# Processor.net
KiCad netlist of a schematic drawn in Altium Designer
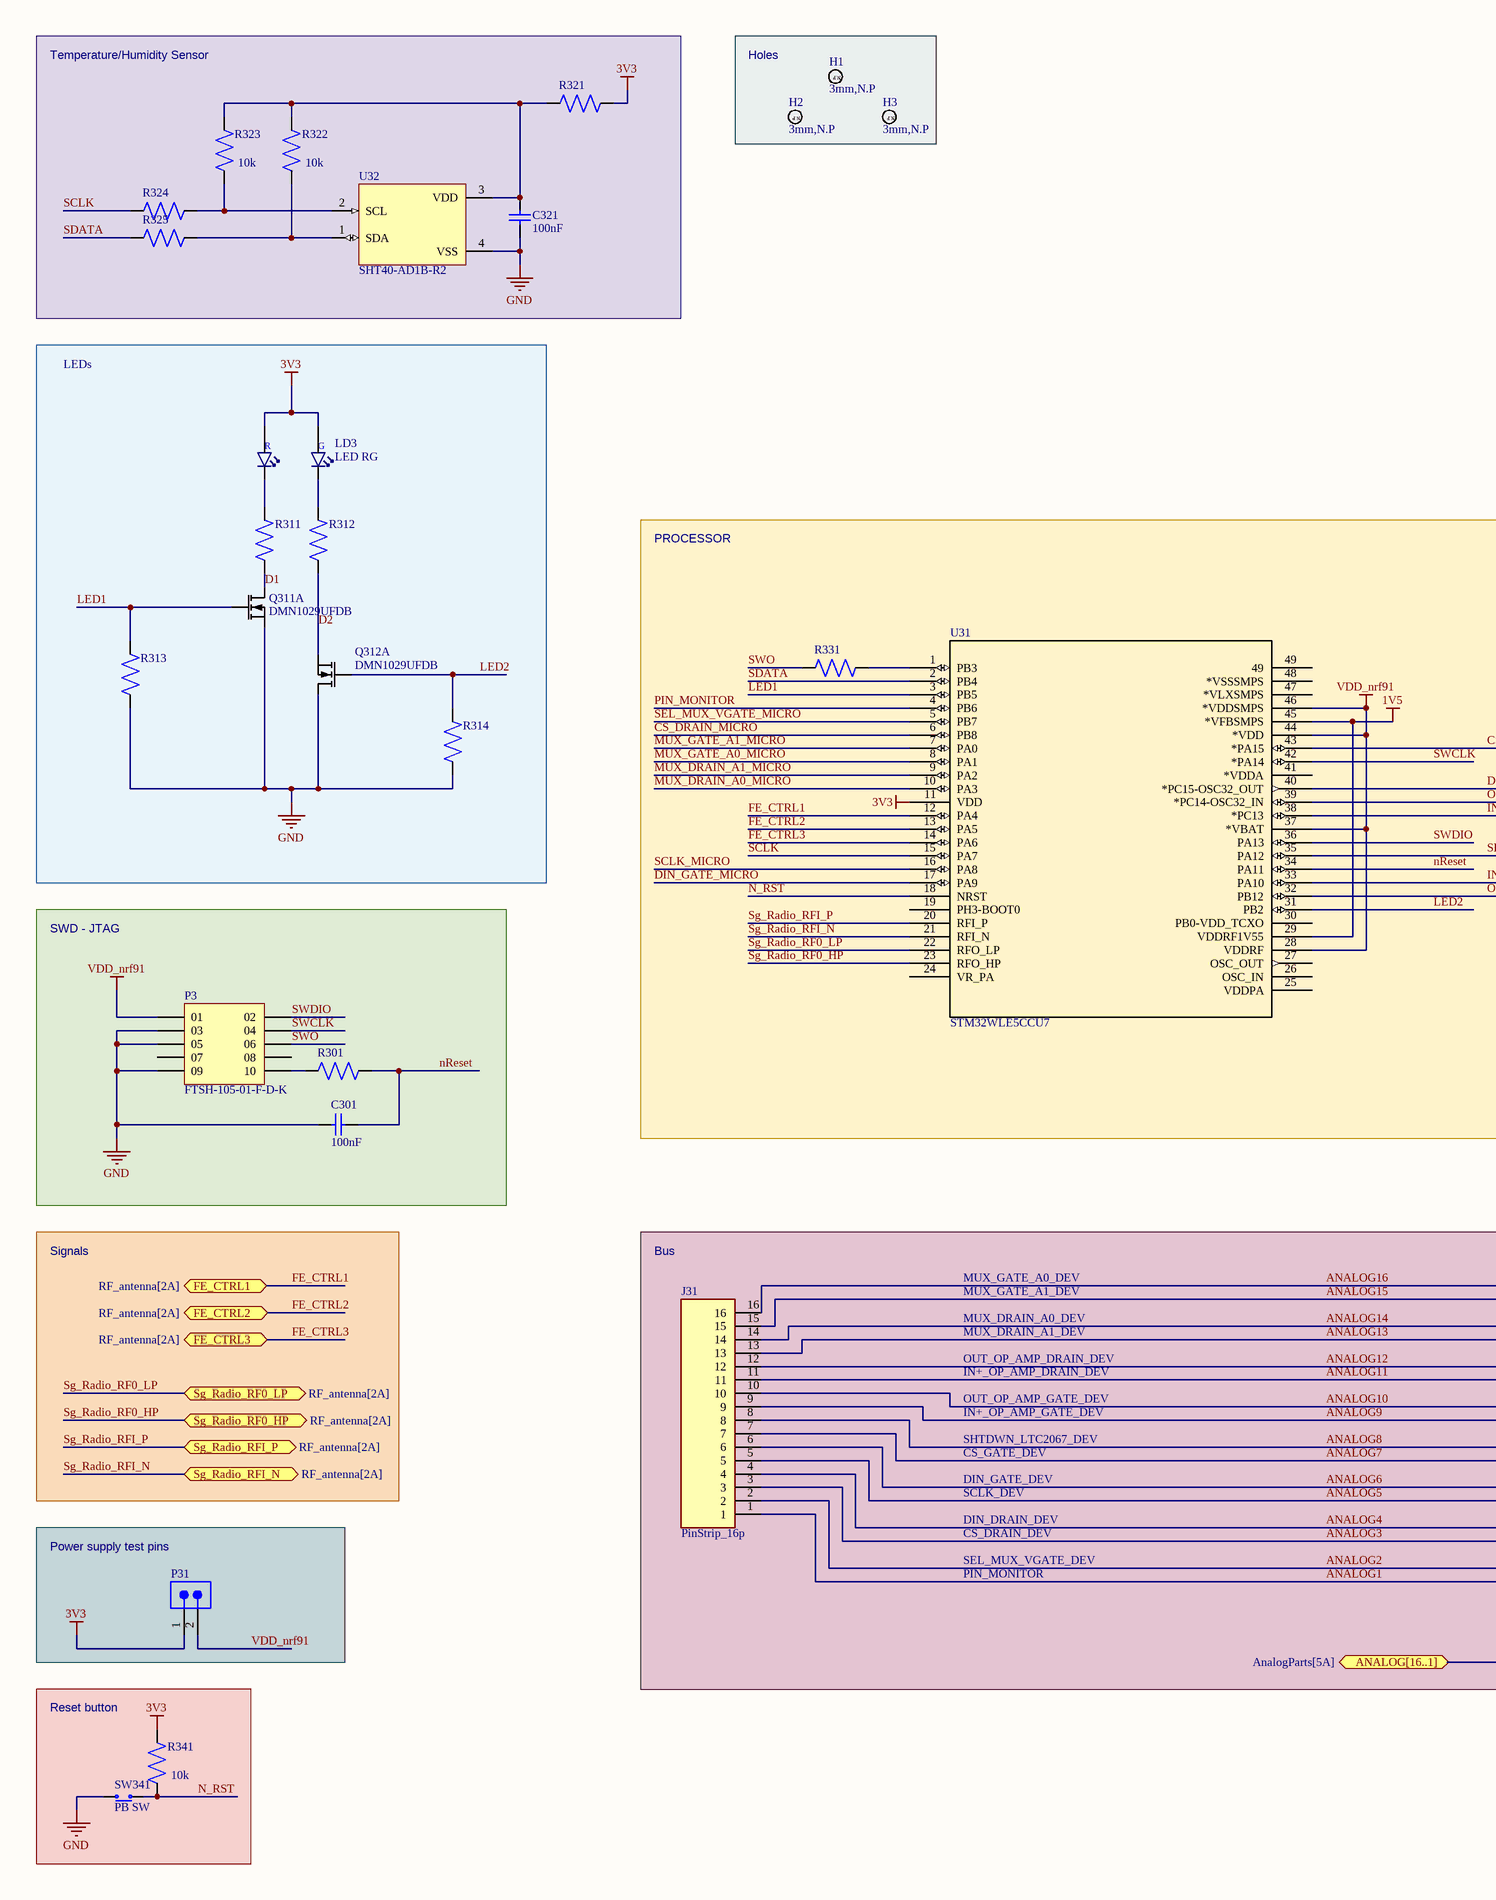
[diagram p0: Processor.SchDoc, left]
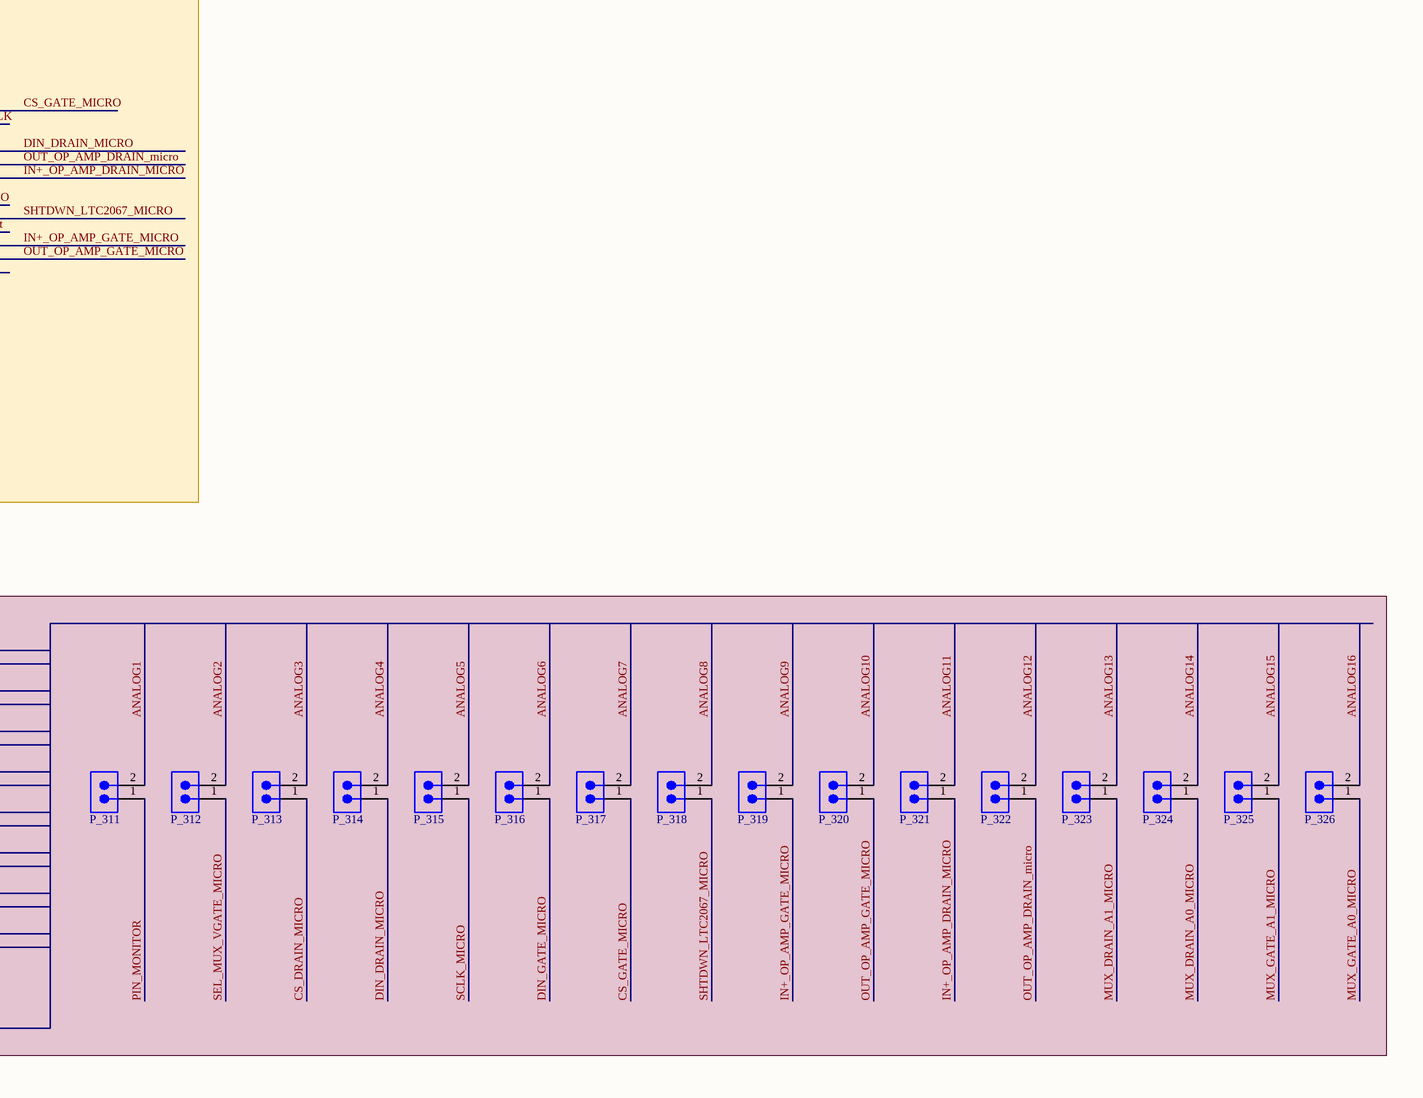
[diagram p1: Processor.SchDoc, right]

(export (version "E")
  (design (tool "Eeschema 10.0.6"))
  (components
    (comp (ref "C301")
      (value "100nF")
      (footprint "CAPC1608X06L")
      (description "Capacitor, X5R, ±10%")
      (libsource (lib "ProgettoAgrifoodLibreriaSCH") (part "C0603-4µ7"))
    )
    (comp (ref "C321")
      (value "100nF")
      (footprint "CAPC1608X06L")
      (description "Capacitor, X5R, ±10%")
      (libsource (lib "ProgettoAgrifoodLibreriaSCH") (part "C0603-4µ7"))
    )
    (comp (ref "H1")
      (value "3mm,N.P")
      (footprint "HOLE_NP_3MM")
      (description "Regular Non-Plated, 3mm hole")
      (libsource (lib "ProgettoAgrifoodLibreriaSCH") (part "Hole_3MM_NP"))
    )
    (comp (ref "H2")
      (value "3mm,N.P")
      (footprint "HOLE_NP_3MM")
      (description "Regular Non-Plated, 3mm hole")
      (libsource (lib "ProgettoAgrifoodLibreriaSCH") (part "Hole_3MM_NP"))
    )
    (comp (ref "H3")
      (value "3mm,N.P")
      (footprint "HOLE_NP_3MM")
      (description "Regular Non-Plated, 3mm hole")
      (libsource (lib "ProgettoAgrifoodLibreriaSCH") (part "Hole_3MM_NP"))
    )
    (comp (ref "J31")
      (value "PinStrip_16p")
      (footprint "PinStrip_16p")
      (description "Connector")
      (fields (field (name "MANUFACTURER_PART_NUMBER") "PH1-16-UA"))
      (libsource (lib "add2") (part "PinStrip_16p"))
    )
    (comp (ref "LD3")
      (value "LED RG")
      (footprint "LED_RGB_0805")
      (description "Red green LED 2 mm x 1.25 mm SMD")
      (libsource (lib "ProgettoAgrifoodLibreriaSCH") (part "APHBM2012LSURKZGKC"))
    )
    (comp (ref "P3")
      (value "FTSH-105-01-F-D-K")
      (footprint "HDR_2x5-THT-1.27mm-K")
      (description "Connector Header Through Hole 10 position 0.050 (1.27mm)")
      (fields (field (name "MF") "Samtec"))
      (libsource (lib "ProgettoAgrifoodLibreriaSCH") (part "Pin Header 2x5 THT, 1.27mm KS"))
    )
    (comp (ref "P31")
      (value "Pin header 2p")
      (footprint "Pin_header_1x2")
      (description "Pin Header, THT, Vertical, pitch 2.54mm, 1 Row, 2P")
      (libsource (lib "ProgettoAgrifoodLibreriaSCH") (part "Pin header 2p"))
    )
    (comp (ref "P_311")
      (value "Pin header 2p")
      (footprint "Pin_header_1x2")
      (description "Pin Header, THT, Vertical, pitch 2.54mm, 1 Row, 2P")
      (libsource (lib "ProgettoAgrifoodLibreriaSCH") (part "Pin header 2p"))
    )
    (comp (ref "P_312")
      (value "Pin header 2p")
      (footprint "Pin_header_1x2")
      (description "Pin Header, THT, Vertical, pitch 2.54mm, 1 Row, 2P")
      (libsource (lib "ProgettoAgrifoodLibreriaSCH") (part "Pin header 2p"))
    )
    (comp (ref "P_313")
      (value "Pin header 2p")
      (footprint "Pin_header_1x2")
      (description "Pin Header, THT, Vertical, pitch 2.54mm, 1 Row, 2P")
      (libsource (lib "ProgettoAgrifoodLibreriaSCH") (part "Pin header 2p"))
    )
    (comp (ref "P_314")
      (value "Pin header 2p")
      (footprint "Pin_header_1x2")
      (description "Pin Header, THT, Vertical, pitch 2.54mm, 1 Row, 2P")
      (libsource (lib "ProgettoAgrifoodLibreriaSCH") (part "Pin header 2p"))
    )
    (comp (ref "P_315")
      (value "Pin header 2p")
      (footprint "Pin_header_1x2")
      (description "Pin Header, THT, Vertical, pitch 2.54mm, 1 Row, 2P")
      (libsource (lib "ProgettoAgrifoodLibreriaSCH") (part "Pin header 2p"))
    )
    (comp (ref "P_316")
      (value "Pin header 2p")
      (footprint "Pin_header_1x2")
      (description "Pin Header, THT, Vertical, pitch 2.54mm, 1 Row, 2P")
      (libsource (lib "ProgettoAgrifoodLibreriaSCH") (part "Pin header 2p"))
    )
    (comp (ref "P_317")
      (value "Pin header 2p")
      (footprint "Pin_header_1x2")
      (description "Pin Header, THT, Vertical, pitch 2.54mm, 1 Row, 2P")
      (libsource (lib "ProgettoAgrifoodLibreriaSCH") (part "Pin header 2p"))
    )
    (comp (ref "P_318")
      (value "Pin header 2p")
      (footprint "Pin_header_1x2")
      (description "Pin Header, THT, Vertical, pitch 2.54mm, 1 Row, 2P")
      (libsource (lib "ProgettoAgrifoodLibreriaSCH") (part "Pin header 2p"))
    )
    (comp (ref "P_319")
      (value "Pin header 2p")
      (footprint "Pin_header_1x2")
      (description "Pin Header, THT, Vertical, pitch 2.54mm, 1 Row, 2P")
      (libsource (lib "ProgettoAgrifoodLibreriaSCH") (part "Pin header 2p"))
    )
    (comp (ref "P_320")
      (value "Pin header 2p")
      (footprint "Pin_header_1x2")
      (description "Pin Header, THT, Vertical, pitch 2.54mm, 1 Row, 2P")
      (libsource (lib "ProgettoAgrifoodLibreriaSCH") (part "Pin header 2p"))
    )
    (comp (ref "P_321")
      (value "Pin header 2p")
      (footprint "Pin_header_1x2")
      (description "Pin Header, THT, Vertical, pitch 2.54mm, 1 Row, 2P")
      (libsource (lib "ProgettoAgrifoodLibreriaSCH") (part "Pin header 2p"))
    )
    (comp (ref "P_322")
      (value "Pin header 2p")
      (footprint "Pin_header_1x2")
      (description "Pin Header, THT, Vertical, pitch 2.54mm, 1 Row, 2P")
      (libsource (lib "ProgettoAgrifoodLibreriaSCH") (part "Pin header 2p"))
    )
    (comp (ref "P_323")
      (value "Pin header 2p")
      (footprint "Pin_header_1x2")
      (description "Pin Header, THT, Vertical, pitch 2.54mm, 1 Row, 2P")
      (libsource (lib "ProgettoAgrifoodLibreriaSCH") (part "Pin header 2p"))
    )
    (comp (ref "P_324")
      (value "Pin header 2p")
      (footprint "Pin_header_1x2")
      (description "Pin Header, THT, Vertical, pitch 2.54mm, 1 Row, 2P")
      (libsource (lib "ProgettoAgrifoodLibreriaSCH") (part "Pin header 2p"))
    )
    (comp (ref "P_325")
      (value "Pin header 2p")
      (footprint "Pin_header_1x2")
      (description "Pin Header, THT, Vertical, pitch 2.54mm, 1 Row, 2P")
      (libsource (lib "ProgettoAgrifoodLibreriaSCH") (part "Pin header 2p"))
    )
    (comp (ref "P_326")
      (value "Pin header 2p")
      (footprint "Pin_header_1x2")
      (description "Pin Header, THT, Vertical, pitch 2.54mm, 1 Row, 2P")
      (libsource (lib "ProgettoAgrifoodLibreriaSCH") (part "Pin header 2p"))
    )
    (comp (ref "Q311")
      (value "DMN1029UFDB")
      (footprint "MOSFET_DMP2160UFDB-7")
      (description "Dual N Ch MOFET, 5.6A, 29mOhm max, 1.4W")
      (libsource (lib "ProgettoAgrifoodLibreriaSCH") (part "DMN1029UFDB"))
    )
    (comp (ref "Q312")
      (value "DMN1029UFDB")
      (footprint "MOSFET_DMP2160UFDB-7")
      (description "Dual N Ch MOFET, 5.6A, 29mOhm max, 1.4W")
      (libsource (lib "ProgettoAgrifoodLibreriaSCH") (part "DMN1029UFDB"))
    )
    (comp (ref "R301")
      (value "~")
      (footprint "RESC1608X04.5L")
      (description "Resistor, ±1%, 0.063W")
      (libsource (lib "ProgettoAgrifoodLibreriaSCH") (part "R0603"))
    )
    (comp (ref "R311")
      (value "~")
      (footprint "RESC1608X04.5L")
      (description "Resistor, ±1%, 0.063W")
      (libsource (lib "ProgettoAgrifoodLibreriaSCH") (part "R0603"))
    )
    (comp (ref "R312")
      (value "~")
      (footprint "RESC1608X04.5L")
      (description "Resistor, ±1%, 0.063W")
      (libsource (lib "ProgettoAgrifoodLibreriaSCH") (part "R0603"))
    )
    (comp (ref "R313")
      (value "~")
      (footprint "RESC1608X04.5L")
      (description "Resistor, ±1%, 0.063W")
      (libsource (lib "ProgettoAgrifoodLibreriaSCH") (part "R0603"))
    )
    (comp (ref "R314")
      (value "~")
      (footprint "RESC1608X04.5L")
      (description "Resistor, ±1%, 0.063W")
      (libsource (lib "ProgettoAgrifoodLibreriaSCH") (part "R0603"))
    )
    (comp (ref "R321")
      (value "~")
      (footprint "RESC1608X04.5L")
      (description "Resistor, ±1%, 0.063W")
      (libsource (lib "ProgettoAgrifoodLibreriaSCH") (part "R0603"))
    )
    (comp (ref "R322")
      (value "10k")
      (footprint "RESC1608X04.5L")
      (description "Resistor, ±1%, 0.063W")
      (libsource (lib "ProgettoAgrifoodLibreriaSCH") (part "R0603"))
    )
    (comp (ref "R323")
      (value "10k")
      (footprint "RESC1608X04.5L")
      (description "Resistor, ±1%, 0.063W")
      (libsource (lib "ProgettoAgrifoodLibreriaSCH") (part "R0603"))
    )
    (comp (ref "R324")
      (value "~")
      (footprint "RESC1608X04.5L")
      (description "Resistor, ±1%, 0.063W")
      (libsource (lib "ProgettoAgrifoodLibreriaSCH") (part "R0603"))
    )
    (comp (ref "R325")
      (value "~")
      (footprint "RESC1608X04.5L")
      (description "Resistor, ±1%, 0.063W")
      (libsource (lib "ProgettoAgrifoodLibreriaSCH") (part "R0603"))
    )
    (comp (ref "R331")
      (value "~")
      (footprint "RESC1608X04.5L")
      (description "Resistor, ±1%, 0.063W")
      (libsource (lib "ProgettoAgrifoodLibreriaSCH") (part "R0603"))
    )
    (comp (ref "R341")
      (value "10k")
      (footprint "RESC1608X04.5L")
      (description "Resistor, ±1%, 0.063W")
      (libsource (lib "ProgettoAgrifoodLibreriaSCH") (part "R0603"))
    )
    (comp (ref "SW341")
      (value "PB SW")
      (footprint "Switch-PB-6.2x6.3mm-SMD")
      (description "Tactile Switch, SPNO, SMD, 160gf, 6.2x6.3x2.5mm")
      (libsource (lib "ProgettoAgrifoodLibreriaSCH") (part "Switch-PB-6.2x6.3mm-SMD"))
    )
    (comp (ref "U31")
      (value "STM32WLE5CCU7")
      (footprint "UFQFPN_5CCU7_STM")
      (description "No Description Available")
      (libsource (lib "STM32WLE5CCU7") (part "STM32WLE5CCU7"))
    )
    (comp (ref "U32")
      (value "SHT40-AD1B-R2")
      (footprint "SHT4X")
      (description "Humidity/Temperature Sensor Digital Serial (I2C) 4-Pin DFN EP T/R")
      (fields (field (name "MF") "Sensirion AG"))
      (libsource (lib "ProgettoAgrifoodLibreriaSCH") (part "SHT40-AD1B-R2"))
    )
  )
  (nets
    (net (code "1") (name "/ANALOG1") (class "Default")
      (node (ref "J31") (pin "1") (pinfunction "1_1") (pintype "passive"))
      (node (ref "P_311") (pin "2") (pinfunction "2_2") (pintype "passive"))
    )
    (net (code "2") (name "/ANALOG2") (class "Default")
      (node (ref "J31") (pin "2") (pinfunction "2_2") (pintype "passive"))
      (node (ref "P_312") (pin "2") (pinfunction "2_2") (pintype "passive"))
    )
    (net (code "3") (name "/ANALOG3") (class "Default")
      (node (ref "J31") (pin "3") (pinfunction "3_3") (pintype "passive"))
      (node (ref "P_313") (pin "2") (pinfunction "2_2") (pintype "passive"))
    )
    (net (code "4") (name "/ANALOG4") (class "Default")
      (node (ref "J31") (pin "4") (pinfunction "4_4") (pintype "passive"))
      (node (ref "P_314") (pin "2") (pinfunction "2_2") (pintype "passive"))
    )
    (net (code "5") (name "/ANALOG5") (class "Default")
      (node (ref "J31") (pin "5") (pinfunction "5_5") (pintype "passive"))
      (node (ref "P_315") (pin "2") (pinfunction "2_2") (pintype "passive"))
    )
    (net (code "6") (name "/ANALOG6") (class "Default")
      (node (ref "J31") (pin "6") (pinfunction "6_6") (pintype "passive"))
      (node (ref "P_316") (pin "2") (pinfunction "2_2") (pintype "passive"))
    )
    (net (code "7") (name "/ANALOG7") (class "Default")
      (node (ref "J31") (pin "7") (pinfunction "7_7") (pintype "passive"))
      (node (ref "P_317") (pin "2") (pinfunction "2_2") (pintype "passive"))
    )
    (net (code "8") (name "/ANALOG8") (class "Default")
      (node (ref "J31") (pin "8") (pinfunction "8_8") (pintype "passive"))
      (node (ref "P_318") (pin "2") (pinfunction "2_2") (pintype "passive"))
    )
    (net (code "9") (name "/ANALOG9") (class "Default")
      (node (ref "J31") (pin "9") (pinfunction "9_9") (pintype "passive"))
      (node (ref "P_319") (pin "2") (pinfunction "2_2") (pintype "passive"))
    )
    (net (code "10") (name "/ANALOG10") (class "Default")
      (node (ref "J31") (pin "10") (pinfunction "10_10") (pintype "passive"))
      (node (ref "P_320") (pin "2") (pinfunction "2_2") (pintype "passive"))
    )
    (net (code "11") (name "/ANALOG11") (class "Default")
      (node (ref "J31") (pin "11") (pinfunction "11_11") (pintype "passive"))
      (node (ref "P_321") (pin "2") (pinfunction "2_2") (pintype "passive"))
    )
    (net (code "12") (name "/ANALOG12") (class "Default")
      (node (ref "J31") (pin "12") (pinfunction "12_12") (pintype "passive"))
      (node (ref "P_322") (pin "2") (pinfunction "2_2") (pintype "passive"))
    )
    (net (code "13") (name "/ANALOG13") (class "Default")
      (node (ref "J31") (pin "13") (pinfunction "13_13") (pintype "passive"))
      (node (ref "P_323") (pin "2") (pinfunction "2_2") (pintype "passive"))
    )
    (net (code "14") (name "/ANALOG14") (class "Default")
      (node (ref "J31") (pin "14") (pinfunction "14_14") (pintype "passive"))
      (node (ref "P_324") (pin "2") (pinfunction "2_2") (pintype "passive"))
    )
    (net (code "15") (name "/ANALOG15") (class "Default")
      (node (ref "J31") (pin "15") (pinfunction "15_15") (pintype "passive"))
      (node (ref "P_325") (pin "2") (pinfunction "2_2") (pintype "passive"))
    )
    (net (code "16") (name "/ANALOG16") (class "Default")
      (node (ref "J31") (pin "16") (pinfunction "16_16") (pintype "passive"))
      (node (ref "P_326") (pin "2") (pinfunction "2_2") (pintype "passive"))
    )
    (net (code "18") (name "/CS_DRAIN_MICRO") (class "Default")
      (node (ref "P_313") (pin "1") (pinfunction "1_1") (pintype "passive"))
      (node (ref "U31") (pin "6") (pinfunction "PB8_6") (pintype "bidirectional"))
    )
    (net (code "19") (name "/CS_GATE_MICRO") (class "Default")
      (node (ref "P_317") (pin "1") (pinfunction "1_1") (pintype "passive"))
      (node (ref "U31") (pin "43") (pinfunction "*PA15_43") (pintype "bidirectional"))
    )
    (net (code "20") (name "/D1") (class "Default")
      (node (ref "Q311") (pin "6") (pinfunction "D1_6") (pintype "passive"))
      (node (ref "R311") (pin "1") (pinfunction "1_1") (pintype "passive"))
    )
    (net (code "21") (name "/D2") (class "Default")
      (node (ref "Q312") (pin "1") (pinfunction "S1_1") (pintype "passive"))
      (node (ref "R312") (pin "1") (pinfunction "1_1") (pintype "passive"))
    )
    (net (code "22") (name "/DIN_DRAIN_MICRO") (class "Default")
      (node (ref "P_314") (pin "1") (pinfunction "1_1") (pintype "passive"))
      (node (ref "U31") (pin "40") (pinfunction "*PC15-OSC32_OUT_40") (pintype "output"))
    )
    (net (code "23") (name "/DIN_GATE_MICRO") (class "Default")
      (node (ref "P_316") (pin "1") (pinfunction "1_1") (pintype "passive"))
      (node (ref "U31") (pin "17") (pinfunction "PA9_17") (pintype "bidirectional"))
    )
    (net (code "24") (name "/FE_CTRL1") (class "Default")
      (node (ref "U31") (pin "12") (pinfunction "PA4_12") (pintype "bidirectional"))
    )
    (net (code "25") (name "/FE_CTRL2") (class "Default")
      (node (ref "U31") (pin "13") (pinfunction "PA5_13") (pintype "bidirectional"))
    )
    (net (code "26") (name "/FE_CTRL3") (class "Default")
      (node (ref "U31") (pin "14") (pinfunction "PA6_14") (pintype "bidirectional"))
    )
    (net (code "27") (name "/IN+_OP_AMP_DRAIN_MICRO") (class "Default")
      (node (ref "P_321") (pin "1") (pinfunction "1_1") (pintype "passive"))
      (node (ref "U31") (pin "38") (pinfunction "*PC13_38") (pintype "bidirectional"))
    )
    (net (code "28") (name "/IN+_OP_AMP_GATE_MICRO") (class "Default")
      (node (ref "P_319") (pin "1") (pinfunction "1_1") (pintype "passive"))
      (node (ref "U31") (pin "33") (pinfunction "PA10_33") (pintype "bidirectional"))
    )
    (net (code "29") (name "/LED1") (class "Default")
      (node (ref "Q311") (pin "2") (pinfunction "G1_2") (pintype "passive"))
      (node (ref "R313") (pin "2") (pinfunction "2_2") (pintype "passive"))
      (node (ref "U31") (pin "3") (pinfunction "PB5_3") (pintype "bidirectional"))
    )
    (net (code "30") (name "/LED2") (class "Default")
      (node (ref "Q312") (pin "2") (pinfunction "G1_2") (pintype "passive"))
      (node (ref "R314") (pin "2") (pinfunction "2_2") (pintype "passive"))
      (node (ref "U31") (pin "31") (pinfunction "PB2_31") (pintype "bidirectional"))
    )
    (net (code "31") (name "/MUX_DRAIN_A0_MICRO") (class "Default")
      (node (ref "P_324") (pin "1") (pinfunction "1_1") (pintype "passive"))
      (node (ref "U31") (pin "10") (pinfunction "PA3_10") (pintype "bidirectional"))
    )
    (net (code "32") (name "/MUX_DRAIN_A1_MICRO") (class "Default")
      (node (ref "P_323") (pin "1") (pinfunction "1_1") (pintype "passive"))
      (node (ref "U31") (pin "9") (pinfunction "PA2_9") (pintype "bidirectional"))
    )
    (net (code "33") (name "/MUX_GATE_A0_MICRO") (class "Default")
      (node (ref "P_326") (pin "1") (pinfunction "1_1") (pintype "passive"))
      (node (ref "U31") (pin "8") (pinfunction "PA1_8") (pintype "bidirectional"))
    )
    (net (code "34") (name "/MUX_GATE_A1_MICRO") (class "Default")
      (node (ref "P_325") (pin "1") (pinfunction "1_1") (pintype "passive"))
      (node (ref "U31") (pin "7") (pinfunction "PA0_7") (pintype "bidirectional"))
    )
    (net (code "35") (name "/N_RST") (class "Default")
      (node (ref "R341") (pin "1") (pinfunction "1_1") (pintype "passive"))
      (node (ref "SW341") (pin "2") (pinfunction "COM_2") (pintype "passive"))
      (node (ref "U31") (pin "18") (pinfunction "NRST_18") (pintype "passive"))
    )
    (net (code "36") (name "/OUT_OP_AMP_DRAIN_micro") (class "Default")
      (node (ref "P_322") (pin "1") (pinfunction "1_1") (pintype "passive"))
      (node (ref "U31") (pin "39") (pinfunction "*PC14-OSC32_IN_39") (pintype "bidirectional"))
    )
    (net (code "37") (name "/OUT_OP_AMP_GATE_MICRO") (class "Default")
      (node (ref "P_320") (pin "1") (pinfunction "1_1") (pintype "passive"))
      (node (ref "U31") (pin "32") (pinfunction "PB12_32") (pintype "bidirectional"))
    )
    (net (code "38") (name "/PIN_MONITOR") (class "Default")
      (node (ref "P_311") (pin "1") (pinfunction "1_1") (pintype "passive"))
      (node (ref "U31") (pin "4") (pinfunction "PB6_4") (pintype "bidirectional"))
    )
    (net (code "39") (name "/SCLK") (class "Default")
      (node (ref "R324") (pin "1") (pinfunction "1_1") (pintype "passive"))
      (node (ref "U31") (pin "15") (pinfunction "PA7_15") (pintype "bidirectional"))
    )
    (net (code "40") (name "/SCLK_MICRO") (class "Default")
      (node (ref "P_315") (pin "1") (pinfunction "1_1") (pintype "passive"))
      (node (ref "U31") (pin "16") (pinfunction "PA8_16") (pintype "bidirectional"))
    )
    (net (code "41") (name "/SDATA") (class "Default")
      (node (ref "R325") (pin "1") (pinfunction "1_1") (pintype "passive"))
      (node (ref "U31") (pin "2") (pinfunction "PB4_2") (pintype "bidirectional"))
    )
    (net (code "42") (name "/SEL_MUX_VGATE_MICRO") (class "Default")
      (node (ref "P_312") (pin "1") (pinfunction "1_1") (pintype "passive"))
      (node (ref "U31") (pin "5") (pinfunction "PB7_5") (pintype "bidirectional"))
    )
    (net (code "43") (name "/SHTDWN_LTC2067_MICRO") (class "Default")
      (node (ref "P_318") (pin "1") (pinfunction "1_1") (pintype "passive"))
      (node (ref "U31") (pin "35") (pinfunction "PA12_35") (pintype "bidirectional"))
    )
    (net (code "44") (name "/SWCLK") (class "Default")
      (node (ref "P3") (pin "04") (pinfunction "04_04") (pintype "passive"))
      (node (ref "U31") (pin "42") (pinfunction "*PA14_42") (pintype "bidirectional"))
    )
    (net (code "45") (name "/SWDIO") (class "Default")
      (node (ref "P3") (pin "02") (pinfunction "02_02") (pintype "passive"))
      (node (ref "U31") (pin "36") (pinfunction "PA13_36") (pintype "bidirectional"))
    )
    (net (code "46") (name "/SWO") (class "Default")
      (node (ref "P3") (pin "06") (pinfunction "06_06") (pintype "passive"))
      (node (ref "R331") (pin "1") (pinfunction "1_1") (pintype "passive"))
    )
    (net (code "47") (name "/Sg_Radio_RF0_HP") (class "Default")
      (node (ref "U31") (pin "23") (pinfunction "RFO_HP_23") (pintype "passive"))
    )
    (net (code "48") (name "/Sg_Radio_RF0_LP") (class "Default")
      (node (ref "U31") (pin "22") (pinfunction "RFO_LP_22") (pintype "passive"))
    )
    (net (code "49") (name "/Sg_Radio_RFI_N") (class "Default")
      (node (ref "U31") (pin "21") (pinfunction "RFI_N_21") (pintype "passive"))
    )
    (net (code "50") (name "/Sg_Radio_RFI_P") (class "Default")
      (node (ref "U31") (pin "20") (pinfunction "RFI_P_20") (pintype "passive"))
    )
    (net (code "51") (name "/nReset") (class "Default")
      (node (ref "C301") (pin "1") (pinfunction "1_1") (pintype "passive"))
      (node (ref "R301") (pin "2") (pinfunction "2_2") (pintype "passive"))
      (node (ref "U31") (pin "34") (pinfunction "PA11_34") (pintype "bidirectional"))
    )
    (net (code "52") (name "1V5") (class "Default")
      (node (ref "U31") (pin "29") (pinfunction "VDDRF1V55_29") (pintype "power_in"))
      (node (ref "U31") (pin "45") (pinfunction "*VFBSMPS_45") (pintype "passive"))
    )
    (net (code "53") (name "3V3") (class "Default")
      (node (ref "LD3") (pin "3") (pinfunction "A_RED_3") (pintype "passive"))
      (node (ref "LD3") (pin "4") (pinfunction "A_GREEN_4") (pintype "passive"))
      (node (ref "P31") (pin "1") (pinfunction "1_1") (pintype "passive"))
      (node (ref "R321") (pin "2") (pinfunction "2_2") (pintype "passive"))
      (node (ref "R341") (pin "2") (pinfunction "2_2") (pintype "passive"))
      (node (ref "U31") (pin "11") (pinfunction "VDD_11") (pintype "power_in"))
    )
    (net (code "54") (name "GND") (class "Default")
      (node (ref "C301") (pin "2") (pinfunction "2_2") (pintype "passive"))
      (node (ref "C321") (pin "1") (pinfunction "1_1") (pintype "passive"))
      (node (ref "P3") (pin "03") (pinfunction "03_03") (pintype "passive"))
      (node (ref "P3") (pin "05") (pinfunction "05_05") (pintype "passive"))
      (node (ref "P3") (pin "09") (pinfunction "09_09") (pintype "passive"))
      (node (ref "Q311") (pin "1") (pinfunction "S1_1") (pintype "passive"))
      (node (ref "Q312") (pin "6") (pinfunction "D1_6") (pintype "passive"))
      (node (ref "R313") (pin "1") (pinfunction "1_1") (pintype "passive"))
      (node (ref "R314") (pin "1") (pinfunction "1_1") (pintype "passive"))
      (node (ref "SW341") (pin "1") (pinfunction "N.O_1") (pintype "passive"))
      (node (ref "U32") (pin "4") (pinfunction "VSS_4") (pintype "power_in"))
    )
    (net (code "55") (name "Net-(LD3-C_GREEN)") (class "Default")
      (node (ref "LD3") (pin "1") (pinfunction "C_GREEN_1") (pintype "passive"))
      (node (ref "R312") (pin "2") (pinfunction "2_2") (pintype "passive"))
    )
    (net (code "56") (name "Net-(LD3-C_RED)") (class "Default")
      (node (ref "LD3") (pin "2") (pinfunction "C_RED_2") (pintype "passive"))
      (node (ref "R311") (pin "2") (pinfunction "2_2") (pintype "passive"))
    )
    (net (code "57") (name "Net-(P3-Pad10)") (class "Default")
      (node (ref "P3") (pin "10") (pinfunction "10_10") (pintype "passive"))
      (node (ref "R301") (pin "1") (pinfunction "1_1") (pintype "passive"))
    )
    (net (code "58") (name "Net-(U31-PB3)") (class "Default")
      (node (ref "R331") (pin "2") (pinfunction "2_2") (pintype "passive"))
      (node (ref "U31") (pin "1") (pinfunction "PB3_1") (pintype "bidirectional"))
    )
    (net (code "59") (name "Net-(U32-SCL)") (class "Default")
      (node (ref "R323") (pin "1") (pinfunction "1_1") (pintype "passive"))
      (node (ref "R324") (pin "2") (pinfunction "2_2") (pintype "passive"))
      (node (ref "U32") (pin "2") (pinfunction "SCL_2") (pintype "input"))
    )
    (net (code "60") (name "Net-(U32-SDA)") (class "Default")
      (node (ref "R322") (pin "1") (pinfunction "1_1") (pintype "passive"))
      (node (ref "R325") (pin "2") (pinfunction "2_2") (pintype "passive"))
      (node (ref "U32") (pin "1") (pinfunction "SDA_1") (pintype "bidirectional"))
    )
    (net (code "61") (name "Net-(U32-VDD)") (class "Default")
      (node (ref "C321") (pin "2") (pinfunction "2_2") (pintype "passive"))
      (node (ref "R321") (pin "1") (pinfunction "1_1") (pintype "passive"))
      (node (ref "R322") (pin "2") (pinfunction "2_2") (pintype "passive"))
      (node (ref "R323") (pin "2") (pinfunction "2_2") (pintype "passive"))
      (node (ref "U32") (pin "3") (pinfunction "VDD_3") (pintype "power_in"))
    )
    (net (code "62") (name "VDD_nrf91") (class "Default")
      (node (ref "P3") (pin "01") (pinfunction "01_01") (pintype "passive"))
      (node (ref "P31") (pin "2") (pinfunction "2_2") (pintype "passive"))
      (node (ref "U31") (pin "28") (pinfunction "VDDRF_28") (pintype "power_in"))
      (node (ref "U31") (pin "37") (pinfunction "*VBAT_37") (pintype "passive"))
      (node (ref "U31") (pin "44") (pinfunction "*VDD_44") (pintype "power_in"))
      (node (ref "U31") (pin "46") (pinfunction "*VDDSMPS_46") (pintype "power_in"))
    )
    (net (code "63") (name "unconnected-(P3-Pad07)") (class "Default")
      (node (ref "P3") (pin "07") (pinfunction "07_07") (pintype "passive"))
    )
    (net (code "64") (name "unconnected-(P3-Pad08)") (class "Default")
      (node (ref "P3") (pin "08") (pinfunction "08_08") (pintype "passive"))
    )
    (net (code "65") (name "unconnected-(U31-*VDDA-Pad41)") (class "Default")
      (node (ref "U31") (pin "41") (pinfunction "*VDDA_41") (pintype "power_in"))
    )
    (net (code "66") (name "unconnected-(U31-*VLXSMPS-Pad47)") (class "Default")
      (node (ref "U31") (pin "47") (pinfunction "*VLXSMPS_47") (pintype "passive"))
    )
    (net (code "67") (name "unconnected-(U31-*VSSSMPS-Pad48)") (class "Default")
      (node (ref "U31") (pin "48") (pinfunction "*VSSSMPS_48") (pintype "power_in"))
    )
    (net (code "68") (name "unconnected-(U31-OSC_IN-Pad26)") (class "Default")
      (node (ref "U31") (pin "26") (pinfunction "OSC_IN_26") (pintype "passive"))
    )
    (net (code "69") (name "unconnected-(U31-OSC_OUT-Pad27)") (class "Default")
      (node (ref "U31") (pin "27") (pinfunction "OSC_OUT_27") (pintype "output"))
    )
    (net (code "70") (name "unconnected-(U31-PB0-VDD_TCXO-Pad30)") (class "Default")
      (node (ref "U31") (pin "30") (pinfunction "PB0-VDD_TCXO_30") (pintype "power_in"))
    )
    (net (code "71") (name "unconnected-(U31-PH3-BOOT0-Pad19)") (class "Default")
      (node (ref "U31") (pin "19") (pinfunction "PH3-BOOT0_19") (pintype "passive"))
    )
    (net (code "72") (name "unconnected-(U31-Pad49)") (class "Default")
      (node (ref "U31") (pin "49") (pinfunction "49_49") (pintype "passive"))
    )
    (net (code "73") (name "unconnected-(U31-VDDPA-Pad25)") (class "Default")
      (node (ref "U31") (pin "25") (pinfunction "VDDPA_25") (pintype "power_in"))
    )
    (net (code "74") (name "unconnected-(U31-VR_PA-Pad24)") (class "Default")
      (node (ref "U31") (pin "24") (pinfunction "VR_PA_24") (pintype "passive"))
    )
  )
)
